# 16F1619DHT11.net
KiCad netlist of a schematic drawn in EAGLE
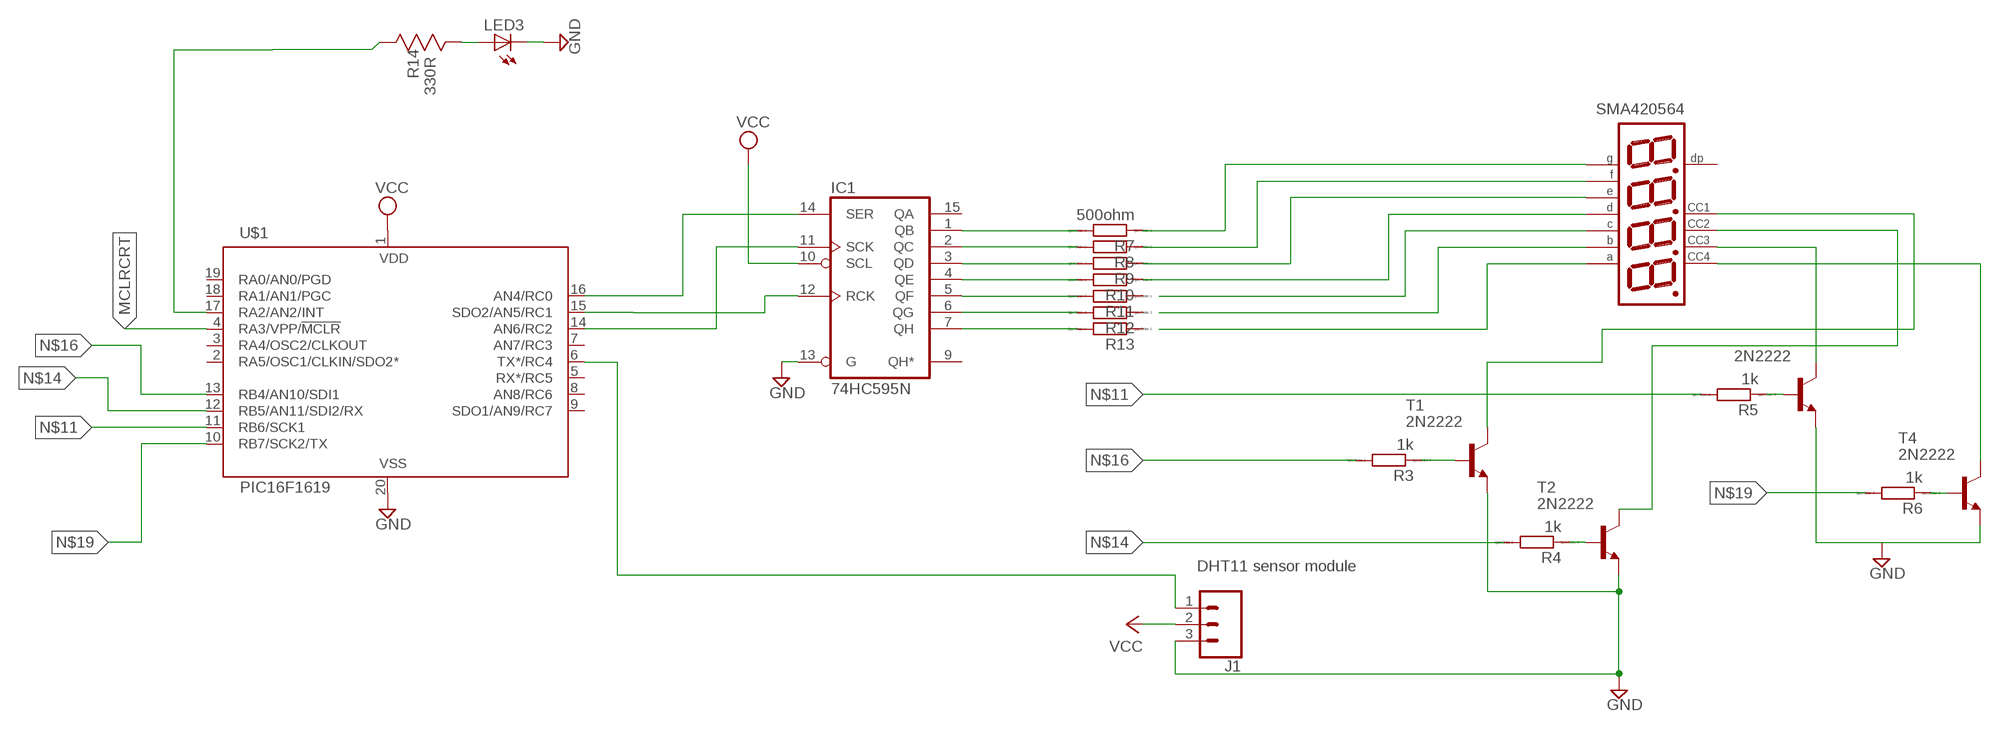
[diagram p0: schematic, sheet 1]

(export (version "E")
  (design (tool "Eeschema 10.0.6"))
  (components
    (comp (ref "IC1")
      (value "74HC595N")
      (footprint "eagle-import:DIL16")
      (libsource (lib "eagle-import") (part "74595NHC"))
    )
    (comp (ref "J1")
      (value "DHT11 sensor module")
      (footprint "eagle-import:1X03-1MM-RA")
      (libsource (lib "eagle-import") (part "CONN_03SMD"))
    )
    (comp (ref "LED3")
      (value "LEDCHIP-LED0603")
      (footprint "eagle-import:CHIP-LED0603")
      (libsource (lib "eagle-import") (part "LEDCHIP-LED0603"))
    )
    (comp (ref "R3")
      (value "1k")
      (footprint "eagle-import:0204_7")
      (libsource (lib "eagle-import") (part "R0204/7"))
    )
    (comp (ref "R4")
      (value "1k")
      (footprint "eagle-import:0204_7")
      (libsource (lib "eagle-import") (part "R0204/7"))
    )
    (comp (ref "R5")
      (value "1k")
      (footprint "eagle-import:0204_7")
      (libsource (lib "eagle-import") (part "R0204/7"))
    )
    (comp (ref "R6")
      (value "1k")
      (footprint "eagle-import:0204_7")
      (libsource (lib "eagle-import") (part "R0204/7"))
    )
    (comp (ref "R7")
      (value "500ohm")
      (footprint "eagle-import:0204_7")
      (libsource (lib "eagle-import") (part "R0204/7"))
    )
    (comp (ref "R8")
      (value "R0204/7")
      (footprint "eagle-import:0204_7")
      (libsource (lib "eagle-import") (part "R0204/7"))
    )
    (comp (ref "R9")
      (value "R0204/7")
      (footprint "eagle-import:0204_7")
      (libsource (lib "eagle-import") (part "R0204/7"))
    )
    (comp (ref "R10")
      (value "R0204/7")
      (footprint "eagle-import:0204_7")
      (libsource (lib "eagle-import") (part "R0204/7"))
    )
    (comp (ref "R11")
      (value "R0204/7")
      (footprint "eagle-import:0204_7")
      (libsource (lib "eagle-import") (part "R0204/7"))
    )
    (comp (ref "R12")
      (value "R0204/7")
      (footprint "eagle-import:0204_7")
      (libsource (lib "eagle-import") (part "R0204/7"))
    )
    (comp (ref "R13")
      (value "R0204/7")
      (footprint "eagle-import:0204_7")
      (libsource (lib "eagle-import") (part "R0204/7"))
    )
    (comp (ref "R14")
      (value "330R")
      (footprint "eagle-import:RESC1608X60N")
      (fields (field (name "MPN") "MC0.063W06031%330R") (field (name "TOLERANCE") "±1%"))
      (libsource (lib "eagle-import") (part "MC0.063W06031%330R"))
    )
    (comp (ref "SMA420564")
      (value "NFD-5641AS")
      (footprint "eagle-import:NFD-5641")
      (libsource (lib "eagle-import") (part "NFD-5641AS"))
    )
    (comp (ref "T1")
      (value "2N2222")
      (footprint "eagle-import:TO18")
      (libsource (lib "eagle-import") (part "2N2222"))
    )
    (comp (ref "T2")
      (value "2N2222")
      (footprint "eagle-import:TO18")
      (libsource (lib "eagle-import") (part "2N2222"))
    )
    (comp (ref "T3")
      (value "2N2222")
      (footprint "eagle-import:TO18")
      (libsource (lib "eagle-import") (part "2N2222"))
    )
    (comp (ref "T4")
      (value "2N2222")
      (footprint "eagle-import:TO18")
      (libsource (lib "eagle-import") (part "2N2222"))
    )
    (comp (ref "U$1")
      (value "PIC16F1619")
      (footprint "eagle-import:SSOP20")
      (libsource (lib "eagle-import") (part "PIC16F1829"))
    )
  )
  (nets
    (net (code "1") (name "GND") (class "Default")
      (node (ref "IC1") (pin "13") (pinfunction "G_13") (pintype "input"))
      (node (ref "J1") (pin "3") (pinfunction "3_3") (pintype "passive"))
      (node (ref "LED3") (pin "C") (pinfunction "C_C") (pintype "passive"))
      (node (ref "T1") (pin "1") (pinfunction "E_1") (pintype "passive"))
      (node (ref "T2") (pin "1") (pinfunction "E_1") (pintype "passive"))
      (node (ref "T3") (pin "1") (pinfunction "E_1") (pintype "passive"))
      (node (ref "T4") (pin "1") (pinfunction "E_1") (pintype "passive"))
      (node (ref "U$1") (pin "20") (pinfunction "VSS_20") (pintype "power_in"))
    )
    (net (code "2") (name "MCLRCRT") (class "Default")
      (node (ref "U$1") (pin "4") (pinfunction "RA3/VPP/~{MCLR}_4") (pintype "input"))
    )
    (net (code "3") (name "N$11") (class "Default")
      (node (ref "R5") (pin "2") (pinfunction "2_2") (pintype "passive"))
      (node (ref "U$1") (pin "11") (pinfunction "RB6/SCK1_11") (pintype "bidirectional"))
    )
    (net (code "4") (name "N$14") (class "Default")
      (node (ref "R4") (pin "2") (pinfunction "2_2") (pintype "passive"))
      (node (ref "U$1") (pin "12") (pinfunction "RB5/AN11/SDI2/RX_12") (pintype "bidirectional"))
    )
    (net (code "5") (name "N$16") (class "Default")
      (node (ref "R3") (pin "2") (pinfunction "2_2") (pintype "passive"))
      (node (ref "U$1") (pin "13") (pinfunction "RB4/AN10/SDI1_13") (pintype "bidirectional"))
    )
    (net (code "6") (name "N$19") (class "Default")
      (node (ref "R6") (pin "2") (pinfunction "2_2") (pintype "passive"))
      (node (ref "U$1") (pin "10") (pinfunction "RB7/SCK2/TX_10") (pintype "bidirectional"))
    )
    (net (code "7") (name "Net-(IC1A-QB)") (class "Default")
      (node (ref "IC1") (pin "1") (pinfunction "QB_1") (pintype "tri_state"))
      (node (ref "R7") (pin "2") (pinfunction "2_2") (pintype "passive"))
    )
    (net (code "8") (name "Net-(IC1A-QC)") (class "Default")
      (node (ref "IC1") (pin "2") (pinfunction "QC_2") (pintype "tri_state"))
      (node (ref "R8") (pin "2") (pinfunction "2_2") (pintype "passive"))
    )
    (net (code "9") (name "Net-(IC1A-QD)") (class "Default")
      (node (ref "IC1") (pin "3") (pinfunction "QD_3") (pintype "tri_state"))
      (node (ref "R9") (pin "2") (pinfunction "2_2") (pintype "passive"))
    )
    (net (code "10") (name "Net-(IC1A-QE)") (class "Default")
      (node (ref "IC1") (pin "4") (pinfunction "QE_4") (pintype "tri_state"))
      (node (ref "R10") (pin "2") (pinfunction "2_2") (pintype "passive"))
    )
    (net (code "11") (name "Net-(IC1A-QF)") (class "Default")
      (node (ref "IC1") (pin "5") (pinfunction "QF_5") (pintype "tri_state"))
      (node (ref "R11") (pin "2") (pinfunction "2_2") (pintype "passive"))
    )
    (net (code "12") (name "Net-(IC1A-QG)") (class "Default")
      (node (ref "IC1") (pin "6") (pinfunction "QG_6") (pintype "tri_state"))
      (node (ref "R12") (pin "2") (pinfunction "2_2") (pintype "passive"))
    )
    (net (code "13") (name "Net-(IC1A-QH)") (class "Default")
      (node (ref "IC1") (pin "7") (pinfunction "QH_7") (pintype "tri_state"))
      (node (ref "R13") (pin "2") (pinfunction "2_2") (pintype "passive"))
    )
    (net (code "14") (name "Net-(IC1A-RCK)") (class "Default")
      (node (ref "IC1") (pin "12") (pinfunction "RCK_12") (pintype "input"))
      (node (ref "U$1") (pin "15") (pinfunction "SDO2/AN5/RC1_15") (pintype "bidirectional"))
    )
    (net (code "15") (name "Net-(IC1A-SCK)") (class "Default")
      (node (ref "IC1") (pin "11") (pinfunction "SCK_11") (pintype "input"))
      (node (ref "U$1") (pin "14") (pinfunction "AN6/RC2_14") (pintype "bidirectional"))
    )
    (net (code "16") (name "Net-(IC1A-SER)") (class "Default")
      (node (ref "IC1") (pin "14") (pinfunction "SER_14") (pintype "input"))
      (node (ref "U$1") (pin "16") (pinfunction "AN4/RC0_16") (pintype "bidirectional"))
    )
    (net (code "17") (name "Net-(R7-Pad1)") (class "Default")
      (node (ref "R7") (pin "1") (pinfunction "1_1") (pintype "passive"))
      (node (ref "SMA420564") (pin "P$5") (pinfunction "P$5_P$5") (pintype "bidirectional"))
    )
    (net (code "18") (name "Net-(R8-Pad1)") (class "Default")
      (node (ref "R8") (pin "1") (pinfunction "1_1") (pintype "passive"))
      (node (ref "SMA420564") (pin "P$10") (pinfunction "P$10_P$10") (pintype "bidirectional"))
    )
    (net (code "19") (name "Net-(R9-Pad1)") (class "Default")
      (node (ref "R9") (pin "1") (pinfunction "1_1") (pintype "passive"))
      (node (ref "SMA420564") (pin "P$1") (pinfunction "P$1_P$1") (pintype "bidirectional"))
    )
    (net (code "20") (name "Net-(R10-Pad1)") (class "Default")
      (node (ref "R10") (pin "1") (pinfunction "1_1") (pintype "passive"))
      (node (ref "SMA420564") (pin "P$2") (pinfunction "P$2_P$2") (pintype "bidirectional"))
    )
    (net (code "21") (name "Net-(R14-R1)") (class "Default")
      (node (ref "R14") (pin "1") (pinfunction "R1_1") (pintype "passive"))
      (node (ref "U$1") (pin "17") (pinfunction "RA2/AN2/INT_17") (pintype "bidirectional"))
    )
    (net (code "22") (name "Net-(R14-R2)") (class "Default")
      (node (ref "LED3") (pin "A") (pinfunction "A_A") (pintype "passive"))
      (node (ref "R14") (pin "2") (pinfunction "R2_2") (pintype "passive"))
    )
    (net (code "23") (name "Net-(T1-B)") (class "Default")
      (node (ref "R3") (pin "1") (pinfunction "1_1") (pintype "passive"))
      (node (ref "T1") (pin "2") (pinfunction "B_2") (pintype "passive"))
    )
    (net (code "24") (name "Net-(T1-C)") (class "Default")
      (node (ref "SMA420564") (pin "P$12") (pinfunction "P$12_P$12") (pintype "bidirectional"))
      (node (ref "T1") (pin "3") (pinfunction "C_3") (pintype "passive"))
    )
    (net (code "25") (name "Net-(T2-B)") (class "Default")
      (node (ref "R4") (pin "1") (pinfunction "1_1") (pintype "passive"))
      (node (ref "T2") (pin "2") (pinfunction "B_2") (pintype "passive"))
    )
    (net (code "26") (name "Net-(T2-C)") (class "Default")
      (node (ref "SMA420564") (pin "P$9") (pinfunction "P$9_P$9") (pintype "bidirectional"))
      (node (ref "T2") (pin "3") (pinfunction "C_3") (pintype "passive"))
    )
    (net (code "27") (name "Net-(T3-B)") (class "Default")
      (node (ref "R5") (pin "1") (pinfunction "1_1") (pintype "passive"))
      (node (ref "T3") (pin "2") (pinfunction "B_2") (pintype "passive"))
    )
    (net (code "28") (name "Net-(T3-C)") (class "Default")
      (node (ref "SMA420564") (pin "P$8") (pinfunction "P$8_P$8") (pintype "bidirectional"))
      (node (ref "T3") (pin "3") (pinfunction "C_3") (pintype "passive"))
    )
    (net (code "29") (name "Net-(T4-B)") (class "Default")
      (node (ref "R6") (pin "1") (pinfunction "1_1") (pintype "passive"))
      (node (ref "T4") (pin "2") (pinfunction "B_2") (pintype "passive"))
    )
    (net (code "30") (name "Net-(T4-C)") (class "Default")
      (node (ref "SMA420564") (pin "P$6") (pinfunction "P$6_P$6") (pintype "bidirectional"))
      (node (ref "T4") (pin "3") (pinfunction "C_3") (pintype "passive"))
    )
    (net (code "31") (name "Net-(U$1-TX*{slash}RC4)") (class "Default")
      (node (ref "J1") (pin "1") (pinfunction "1_1") (pintype "passive"))
      (node (ref "U$1") (pin "6") (pinfunction "TX*/RC4_6") (pintype "bidirectional"))
    )
    (net (code "32") (name "VCC") (class "Default")
      (node (ref "IC1") (pin "10") (pinfunction "SCL_10") (pintype "input"))
      (node (ref "J1") (pin "2") (pinfunction "2_2") (pintype "passive"))
      (node (ref "U$1") (pin "1") (pinfunction "VDD_1") (pintype "power_in"))
    )
    (net (code "33") (name "unconnected-(IC1A-QA-Pad15)") (class "Default")
      (node (ref "IC1") (pin "15") (pinfunction "QA_15") (pintype "tri_state"))
    )
    (net (code "34") (name "unconnected-(IC1A-QH*-Pad9)") (class "Default")
      (node (ref "IC1") (pin "9") (pinfunction "QH*_9") (pintype "tri_state"))
    )
    (net (code "35") (name "unconnected-(R11-Pad1)") (class "Default")
      (node (ref "R11") (pin "1") (pinfunction "1_1") (pintype "passive"))
    )
    (net (code "36") (name "unconnected-(R12-Pad1)") (class "Default")
      (node (ref "R12") (pin "1") (pinfunction "1_1") (pintype "passive"))
    )
    (net (code "37") (name "unconnected-(R13-Pad1)") (class "Default")
      (node (ref "R13") (pin "1") (pinfunction "1_1") (pintype "passive"))
    )
    (net (code "38") (name "unconnected-(SMA420564-PadP$3)") (class "Default")
      (node (ref "SMA420564") (pin "P$3") (pinfunction "P$3_P$3") (pintype "bidirectional"))
    )
    (net (code "39") (name "unconnected-(SMA420564-PadP$4)") (class "Default")
      (node (ref "SMA420564") (pin "P$4") (pinfunction "P$4_P$4") (pintype "bidirectional"))
    )
    (net (code "40") (name "unconnected-(SMA420564-PadP$7)") (class "Default")
      (node (ref "SMA420564") (pin "P$7") (pinfunction "P$7_P$7") (pintype "bidirectional"))
    )
    (net (code "41") (name "unconnected-(SMA420564-PadP$11)") (class "Default")
      (node (ref "SMA420564") (pin "P$11") (pinfunction "P$11_P$11") (pintype "bidirectional"))
    )
    (net (code "42") (name "unconnected-(U$1-AN7{slash}RC3-Pad7)") (class "Default")
      (node (ref "U$1") (pin "7") (pinfunction "AN7/RC3_7") (pintype "bidirectional"))
    )
    (net (code "43") (name "unconnected-(U$1-AN8{slash}RC6-Pad8)") (class "Default")
      (node (ref "U$1") (pin "8") (pinfunction "AN8/RC6_8") (pintype "bidirectional"))
    )
    (net (code "44") (name "unconnected-(U$1-RA0{slash}AN0{slash}PGD-Pad19)") (class "Default")
      (node (ref "U$1") (pin "19") (pinfunction "RA0/AN0/PGD_19") (pintype "bidirectional"))
    )
    (net (code "45") (name "unconnected-(U$1-RA1{slash}AN1{slash}PGC-Pad18)") (class "Default")
      (node (ref "U$1") (pin "18") (pinfunction "RA1/AN1/PGC_18") (pintype "bidirectional"))
    )
    (net (code "46") (name "unconnected-(U$1-RA4{slash}OSC2{slash}CLKOUT-Pad3)") (class "Default")
      (node (ref "U$1") (pin "3") (pinfunction "RA4/OSC2/CLKOUT_3") (pintype "bidirectional"))
    )
    (net (code "47") (name "unconnected-(U$1-RA5{slash}OSC1{slash}CLKIN{slash}SDO2*-Pad2)") (class "Default")
      (node (ref "U$1") (pin "2") (pinfunction "RA5/OSC1/CLKIN/SDO2*_2") (pintype "bidirectional"))
    )
    (net (code "48") (name "unconnected-(U$1-RX*{slash}RC5-Pad5)") (class "Default")
      (node (ref "U$1") (pin "5") (pinfunction "RX*/RC5_5") (pintype "bidirectional"))
    )
    (net (code "49") (name "unconnected-(U$1-SDO1{slash}AN9{slash}RC7-Pad9)") (class "Default")
      (node (ref "U$1") (pin "9") (pinfunction "SDO1/AN9/RC7_9") (pintype "bidirectional"))
    )
  )
)
